# HVAC8new.net
KiCad netlist of a schematic drawn in EAGLE
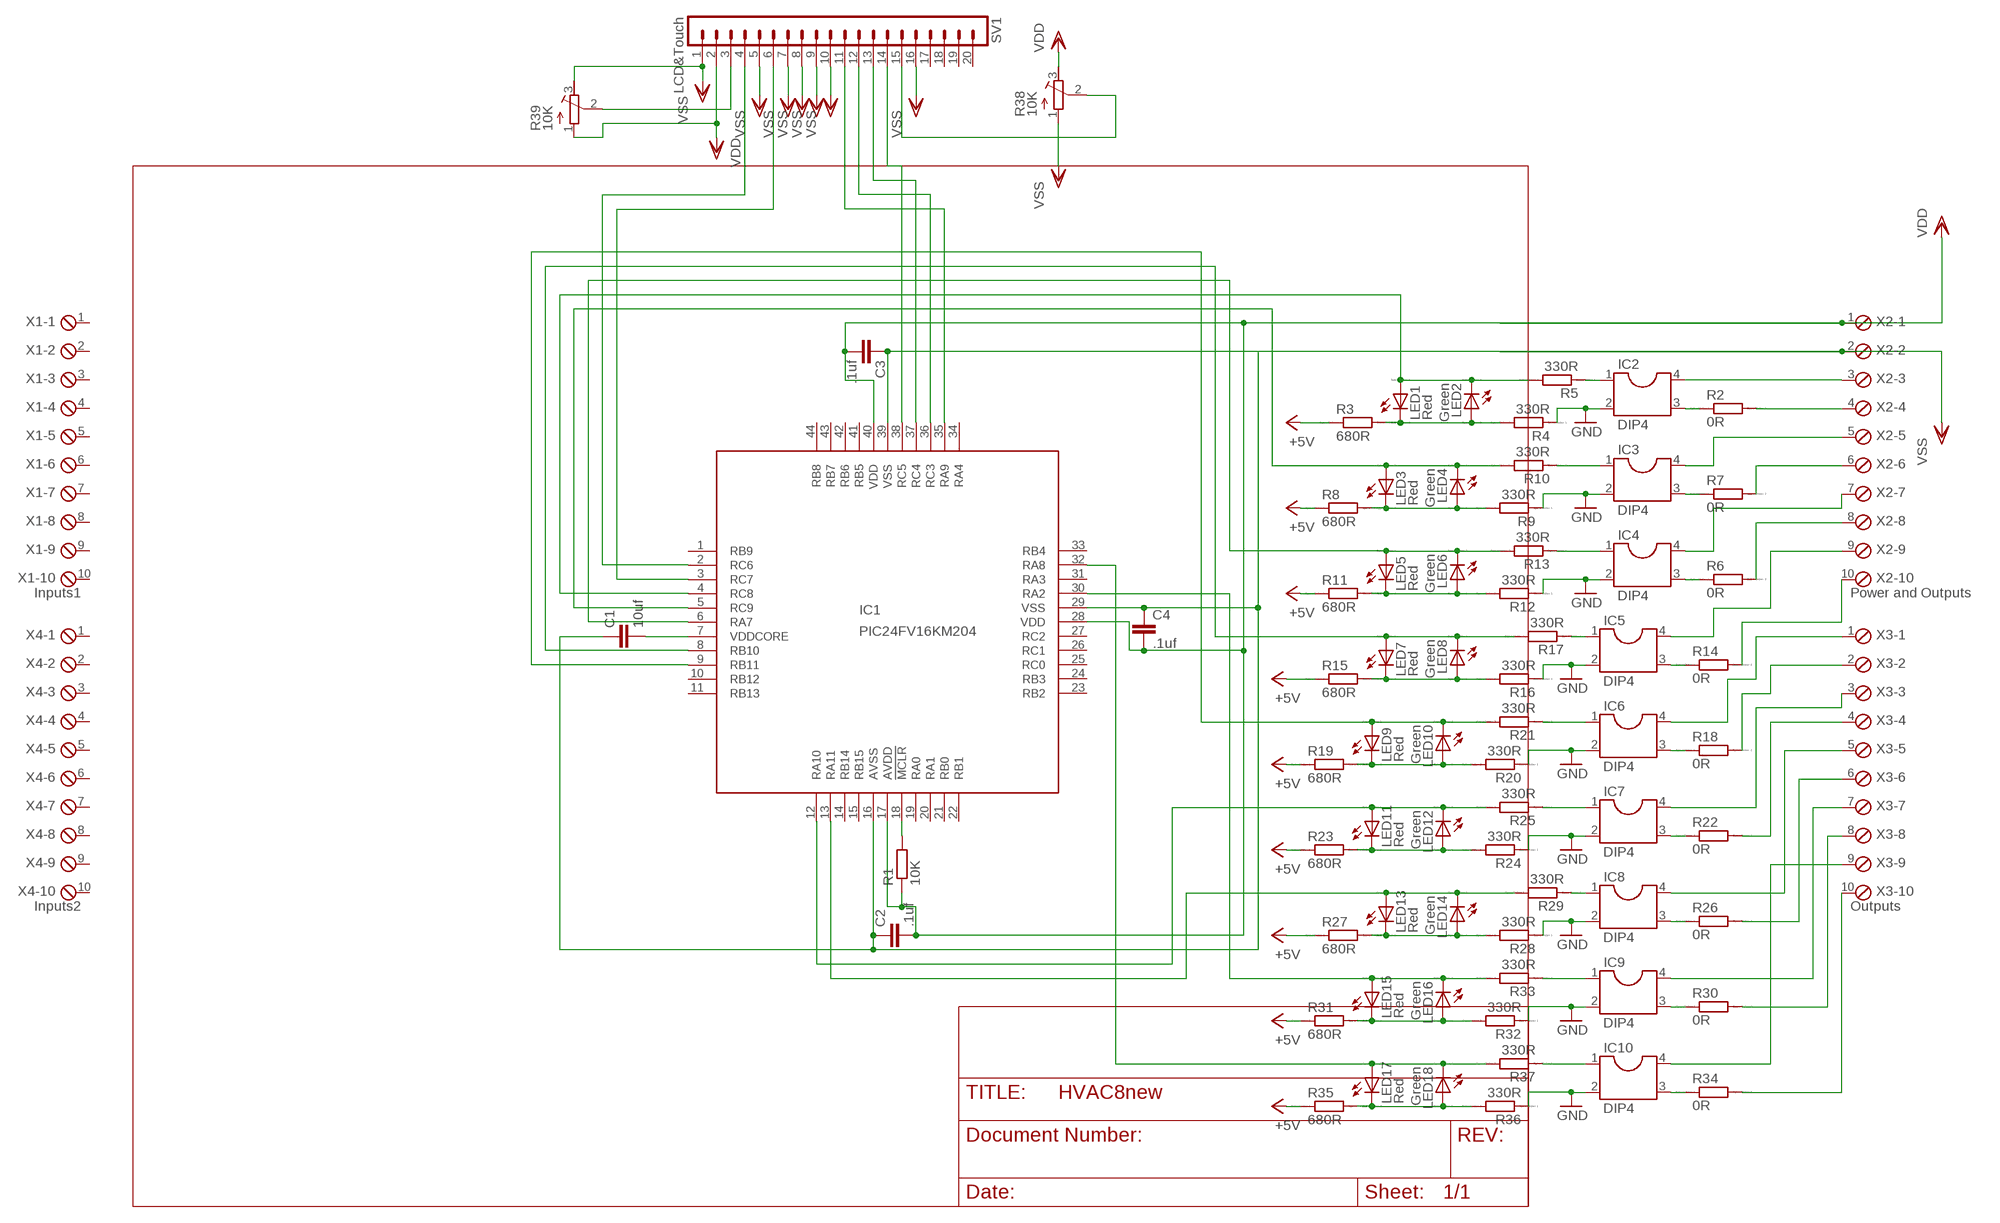
[diagram p0: schematic, sheet 1]

(export (version "E")
  (design (tool "Eeschema 10.0.6"))
  (components
    (comp (ref "C1")
      (value "10uf")
      (footprint "eagle-import:C1206")
      (libsource (lib "eagle-import") (part "C-EUC1206"))
    )
    (comp (ref "C2")
      (value ".1uf")
      (footprint "eagle-import:C1206")
      (libsource (lib "eagle-import") (part "C-EUC1206"))
    )
    (comp (ref "C3")
      (value ".1uf")
      (footprint "eagle-import:C1206")
      (libsource (lib "eagle-import") (part "C-EUC1206"))
    )
    (comp (ref "C4")
      (value ".1uf")
      (footprint "eagle-import:C1206")
      (libsource (lib "eagle-import") (part "C-EUC1206"))
    )
    (comp (ref "IC1")
      (value "PIC24FV16KM204")
      (footprint "eagle-import:TQFP44")
      (libsource (lib "eagle-import") (part "PIC24FV16KM204"))
    )
    (comp (ref "IC2")
      (value "DIP4")
      (footprint "eagle-import:SOCKET-04")
      (libsource (lib "eagle-import") (part "DIL4S"))
    )
    (comp (ref "IC3")
      (value "DIP4")
      (footprint "eagle-import:SOCKET-04")
      (libsource (lib "eagle-import") (part "DIL4S"))
    )
    (comp (ref "IC4")
      (value "DIP4")
      (footprint "eagle-import:SOCKET-04")
      (libsource (lib "eagle-import") (part "DIL4S"))
    )
    (comp (ref "IC5")
      (value "DIP4")
      (footprint "eagle-import:SOCKET-04")
      (libsource (lib "eagle-import") (part "DIL4S"))
    )
    (comp (ref "IC6")
      (value "DIP4")
      (footprint "eagle-import:SOCKET-04")
      (libsource (lib "eagle-import") (part "DIL4S"))
    )
    (comp (ref "IC7")
      (value "DIP4")
      (footprint "eagle-import:SOCKET-04")
      (libsource (lib "eagle-import") (part "DIL4S"))
    )
    (comp (ref "IC8")
      (value "DIP4")
      (footprint "eagle-import:SOCKET-04")
      (libsource (lib "eagle-import") (part "DIL4S"))
    )
    (comp (ref "IC9")
      (value "DIP4")
      (footprint "eagle-import:SOCKET-04")
      (libsource (lib "eagle-import") (part "DIL4S"))
    )
    (comp (ref "IC10")
      (value "DIP4")
      (footprint "eagle-import:SOCKET-04")
      (libsource (lib "eagle-import") (part "DIL4S"))
    )
    (comp (ref "LED1")
      (value "Red")
      (footprint "eagle-import:LED_1206")
      (libsource (lib "eagle-import") (part "LED_E"))
    )
    (comp (ref "LED2")
      (value "Green")
      (footprint "eagle-import:LED_1206")
      (libsource (lib "eagle-import") (part "LED_E"))
    )
    (comp (ref "LED3")
      (value "Red")
      (footprint "eagle-import:LED_1206")
      (libsource (lib "eagle-import") (part "LED_E"))
    )
    (comp (ref "LED4")
      (value "Green")
      (footprint "eagle-import:LED_1206")
      (libsource (lib "eagle-import") (part "LED_E"))
    )
    (comp (ref "LED5")
      (value "Red")
      (footprint "eagle-import:LED_1206")
      (libsource (lib "eagle-import") (part "LED_E"))
    )
    (comp (ref "LED6")
      (value "Green")
      (footprint "eagle-import:LED_1206")
      (libsource (lib "eagle-import") (part "LED_E"))
    )
    (comp (ref "LED7")
      (value "Red")
      (footprint "eagle-import:LED_1206")
      (libsource (lib "eagle-import") (part "LED_E"))
    )
    (comp (ref "LED8")
      (value "Green")
      (footprint "eagle-import:LED_1206")
      (libsource (lib "eagle-import") (part "LED_E"))
    )
    (comp (ref "LED9")
      (value "Red")
      (footprint "eagle-import:LED_1206")
      (libsource (lib "eagle-import") (part "LED_E"))
    )
    (comp (ref "LED10")
      (value "Green")
      (footprint "eagle-import:LED_1206")
      (libsource (lib "eagle-import") (part "LED_E"))
    )
    (comp (ref "LED11")
      (value "Red")
      (footprint "eagle-import:LED_1206")
      (libsource (lib "eagle-import") (part "LED_E"))
    )
    (comp (ref "LED12")
      (value "Green")
      (footprint "eagle-import:LED_1206")
      (libsource (lib "eagle-import") (part "LED_E"))
    )
    (comp (ref "LED13")
      (value "Red")
      (footprint "eagle-import:LED_1206")
      (libsource (lib "eagle-import") (part "LED_E"))
    )
    (comp (ref "LED14")
      (value "Green")
      (footprint "eagle-import:LED_1206")
      (libsource (lib "eagle-import") (part "LED_E"))
    )
    (comp (ref "LED15")
      (value "Red")
      (footprint "eagle-import:LED_1206")
      (libsource (lib "eagle-import") (part "LED_E"))
    )
    (comp (ref "LED16")
      (value "Green")
      (footprint "eagle-import:LED_1206")
      (libsource (lib "eagle-import") (part "LED_E"))
    )
    (comp (ref "LED17")
      (value "Red")
      (footprint "eagle-import:LED_1206")
      (libsource (lib "eagle-import") (part "LED_E"))
    )
    (comp (ref "LED18")
      (value "Green")
      (footprint "eagle-import:LED_1206")
      (libsource (lib "eagle-import") (part "LED_E"))
    )
    (comp (ref "R1")
      (value "10K")
      (footprint "eagle-import:R1206")
      (libsource (lib "eagle-import") (part "R-EU_R1206"))
    )
    (comp (ref "R2")
      (value "0R")
      (footprint "eagle-import:R1206")
      (libsource (lib "eagle-import") (part "RR1206"))
    )
    (comp (ref "R3")
      (value "680R")
      (footprint "eagle-import:R1206")
      (libsource (lib "eagle-import") (part "RR1206"))
    )
    (comp (ref "R4")
      (value "330R")
      (footprint "eagle-import:R1206")
      (libsource (lib "eagle-import") (part "RR1206"))
    )
    (comp (ref "R5")
      (value "330R")
      (footprint "eagle-import:R1206")
      (libsource (lib "eagle-import") (part "RR1206"))
    )
    (comp (ref "R6")
      (value "0R")
      (footprint "eagle-import:R1206")
      (libsource (lib "eagle-import") (part "RR1206"))
    )
    (comp (ref "R7")
      (value "0R")
      (footprint "eagle-import:R1206")
      (libsource (lib "eagle-import") (part "RR1206"))
    )
    (comp (ref "R8")
      (value "680R")
      (footprint "eagle-import:R1206")
      (libsource (lib "eagle-import") (part "RR1206"))
    )
    (comp (ref "R9")
      (value "330R")
      (footprint "eagle-import:R1206")
      (libsource (lib "eagle-import") (part "RR1206"))
    )
    (comp (ref "R10")
      (value "330R")
      (footprint "eagle-import:R1206")
      (libsource (lib "eagle-import") (part "RR1206"))
    )
    (comp (ref "R11")
      (value "680R")
      (footprint "eagle-import:R1206")
      (libsource (lib "eagle-import") (part "RR1206"))
    )
    (comp (ref "R12")
      (value "330R")
      (footprint "eagle-import:R1206")
      (libsource (lib "eagle-import") (part "RR1206"))
    )
    (comp (ref "R13")
      (value "330R")
      (footprint "eagle-import:R1206")
      (libsource (lib "eagle-import") (part "RR1206"))
    )
    (comp (ref "R14")
      (value "0R")
      (footprint "eagle-import:R1206")
      (libsource (lib "eagle-import") (part "RR1206"))
    )
    (comp (ref "R15")
      (value "680R")
      (footprint "eagle-import:R1206")
      (libsource (lib "eagle-import") (part "RR1206"))
    )
    (comp (ref "R16")
      (value "330R")
      (footprint "eagle-import:R1206")
      (libsource (lib "eagle-import") (part "RR1206"))
    )
    (comp (ref "R17")
      (value "330R")
      (footprint "eagle-import:R1206")
      (libsource (lib "eagle-import") (part "RR1206"))
    )
    (comp (ref "R18")
      (value "0R")
      (footprint "eagle-import:R1206")
      (libsource (lib "eagle-import") (part "RR1206"))
    )
    (comp (ref "R19")
      (value "680R")
      (footprint "eagle-import:R1206")
      (libsource (lib "eagle-import") (part "RR1206"))
    )
    (comp (ref "R20")
      (value "330R")
      (footprint "eagle-import:R1206")
      (libsource (lib "eagle-import") (part "RR1206"))
    )
    (comp (ref "R21")
      (value "330R")
      (footprint "eagle-import:R1206")
      (libsource (lib "eagle-import") (part "RR1206"))
    )
    (comp (ref "R22")
      (value "0R")
      (footprint "eagle-import:R1206")
      (libsource (lib "eagle-import") (part "RR1206"))
    )
    (comp (ref "R23")
      (value "680R")
      (footprint "eagle-import:R1206")
      (libsource (lib "eagle-import") (part "RR1206"))
    )
    (comp (ref "R24")
      (value "330R")
      (footprint "eagle-import:R1206")
      (libsource (lib "eagle-import") (part "RR1206"))
    )
    (comp (ref "R25")
      (value "330R")
      (footprint "eagle-import:R1206")
      (libsource (lib "eagle-import") (part "RR1206"))
    )
    (comp (ref "R26")
      (value "0R")
      (footprint "eagle-import:R1206")
      (libsource (lib "eagle-import") (part "RR1206"))
    )
    (comp (ref "R27")
      (value "680R")
      (footprint "eagle-import:R1206")
      (libsource (lib "eagle-import") (part "RR1206"))
    )
    (comp (ref "R28")
      (value "330R")
      (footprint "eagle-import:R1206")
      (libsource (lib "eagle-import") (part "RR1206"))
    )
    (comp (ref "R29")
      (value "330R")
      (footprint "eagle-import:R1206")
      (libsource (lib "eagle-import") (part "RR1206"))
    )
    (comp (ref "R30")
      (value "0R")
      (footprint "eagle-import:R1206")
      (libsource (lib "eagle-import") (part "RR1206"))
    )
    (comp (ref "R31")
      (value "680R")
      (footprint "eagle-import:R1206")
      (libsource (lib "eagle-import") (part "RR1206"))
    )
    (comp (ref "R32")
      (value "330R")
      (footprint "eagle-import:R1206")
      (libsource (lib "eagle-import") (part "RR1206"))
    )
    (comp (ref "R33")
      (value "330R")
      (footprint "eagle-import:R1206")
      (libsource (lib "eagle-import") (part "RR1206"))
    )
    (comp (ref "R34")
      (value "0R")
      (footprint "eagle-import:R1206")
      (libsource (lib "eagle-import") (part "RR1206"))
    )
    (comp (ref "R35")
      (value "680R")
      (footprint "eagle-import:R1206")
      (libsource (lib "eagle-import") (part "RR1206"))
    )
    (comp (ref "R36")
      (value "330R")
      (footprint "eagle-import:R1206")
      (libsource (lib "eagle-import") (part "RR1206"))
    )
    (comp (ref "R37")
      (value "330R")
      (footprint "eagle-import:R1206")
      (libsource (lib "eagle-import") (part "RR1206"))
    )
    (comp (ref "R38")
      (value "10K")
      (footprint "eagle-import:RTRIM3296W")
      (libsource (lib "eagle-import") (part "R-TRIMM3296W"))
    )
    (comp (ref "R39")
      (value "10K")
      (footprint "eagle-import:RTRIM3296W")
      (libsource (lib "eagle-import") (part "R-TRIMM3296W"))
    )
    (comp (ref "SV1")
      (value "LCD&Touch")
      (footprint "eagle-import:MA20-1")
      (libsource (lib "eagle-import") (part "MA20-1"))
    )
    (comp (ref "X1")
      (value "Inputs1")
      (footprint "eagle-import:10POL254")
      (libsource (lib "eagle-import") (part "MPT10"))
    )
    (comp (ref "X2")
      (value "Power and Outputs")
      (footprint "eagle-import:10POL254")
      (libsource (lib "eagle-import") (part "MPT10"))
    )
    (comp (ref "X3")
      (value "Outputs")
      (footprint "eagle-import:10POL254")
      (libsource (lib "eagle-import") (part "MPT10"))
    )
    (comp (ref "X4")
      (value "Inputs2")
      (footprint "eagle-import:10POL254")
      (libsource (lib "eagle-import") (part "MPT10"))
    )
  )
  (nets
    (net (code "1") (name "+5V") (class "Default")
      (node (ref "R11") (pin "1") (pinfunction "1_1") (pintype "passive"))
      (node (ref "R15") (pin "1") (pinfunction "1_1") (pintype "passive"))
      (node (ref "R19") (pin "1") (pinfunction "1_1") (pintype "passive"))
      (node (ref "R23") (pin "1") (pinfunction "1_1") (pintype "passive"))
      (node (ref "R27") (pin "1") (pinfunction "1_1") (pintype "passive"))
      (node (ref "R3") (pin "1") (pinfunction "1_1") (pintype "passive"))
      (node (ref "R31") (pin "1") (pinfunction "1_1") (pintype "passive"))
      (node (ref "R35") (pin "1") (pinfunction "1_1") (pintype "passive"))
      (node (ref "R8") (pin "1") (pinfunction "1_1") (pintype "passive"))
    )
    (net (code "2") (name "GND") (class "Default")
      (node (ref "IC10") (pin "2") (pinfunction "2_2") (pintype "passive"))
      (node (ref "IC2") (pin "2") (pinfunction "2_2") (pintype "passive"))
      (node (ref "IC3") (pin "2") (pinfunction "2_2") (pintype "passive"))
      (node (ref "IC4") (pin "2") (pinfunction "2_2") (pintype "passive"))
      (node (ref "IC5") (pin "2") (pinfunction "2_2") (pintype "passive"))
      (node (ref "IC6") (pin "2") (pinfunction "2_2") (pintype "passive"))
      (node (ref "IC7") (pin "2") (pinfunction "2_2") (pintype "passive"))
      (node (ref "IC8") (pin "2") (pinfunction "2_2") (pintype "passive"))
      (node (ref "IC9") (pin "2") (pinfunction "2_2") (pintype "passive"))
      (node (ref "R12") (pin "1") (pinfunction "1_1") (pintype "passive"))
      (node (ref "R16") (pin "1") (pinfunction "1_1") (pintype "passive"))
      (node (ref "R20") (pin "1") (pinfunction "1_1") (pintype "passive"))
      (node (ref "R24") (pin "1") (pinfunction "1_1") (pintype "passive"))
      (node (ref "R28") (pin "1") (pinfunction "1_1") (pintype "passive"))
      (node (ref "R32") (pin "1") (pinfunction "1_1") (pintype "passive"))
      (node (ref "R36") (pin "1") (pinfunction "1_1") (pintype "passive"))
      (node (ref "R4") (pin "1") (pinfunction "1_1") (pintype "passive"))
      (node (ref "R9") (pin "1") (pinfunction "1_1") (pintype "passive"))
    )
    (net (code "3") (name "Net-(IC1-RA2)") (class "Default")
      (node (ref "IC1") (pin "30") (pinfunction "RA2_30") (pintype "bidirectional"))
      (node (ref "LED15") (pin "A") (pinfunction "A_A") (pintype "passive"))
      (node (ref "LED16") (pin "C") (pinfunction "C_C") (pintype "passive"))
      (node (ref "R33") (pin "2") (pinfunction "2_2") (pintype "passive"))
    )
    (net (code "4") (name "Net-(IC1-RA7)") (class "Default")
      (node (ref "IC1") (pin "6") (pinfunction "RA7_6") (pintype "bidirectional"))
      (node (ref "LED5") (pin "A") (pinfunction "A_A") (pintype "passive"))
      (node (ref "LED6") (pin "C") (pinfunction "C_C") (pintype "passive"))
      (node (ref "R13") (pin "2") (pinfunction "2_2") (pintype "passive"))
    )
    (net (code "5") (name "Net-(IC1-RA8)") (class "Default")
      (node (ref "IC1") (pin "32") (pinfunction "RA8_32") (pintype "bidirectional"))
      (node (ref "LED17") (pin "A") (pinfunction "A_A") (pintype "passive"))
      (node (ref "LED18") (pin "C") (pinfunction "C_C") (pintype "passive"))
      (node (ref "R37") (pin "2") (pinfunction "2_2") (pintype "passive"))
    )
    (net (code "6") (name "Net-(IC1-RA9)") (class "Default")
      (node (ref "IC1") (pin "35") (pinfunction "RA9_35") (pintype "bidirectional"))
      (node (ref "SV1") (pin "11") (pinfunction "11_11") (pintype "passive"))
    )
    (net (code "7") (name "Net-(IC1-RA10)") (class "Default")
      (node (ref "IC1") (pin "12") (pinfunction "RA10_12") (pintype "bidirectional"))
      (node (ref "LED11") (pin "A") (pinfunction "A_A") (pintype "passive"))
      (node (ref "LED12") (pin "C") (pinfunction "C_C") (pintype "passive"))
      (node (ref "R25") (pin "2") (pinfunction "2_2") (pintype "passive"))
    )
    (net (code "8") (name "Net-(IC1-RA11)") (class "Default")
      (node (ref "IC1") (pin "13") (pinfunction "RA11_13") (pintype "bidirectional"))
      (node (ref "LED13") (pin "A") (pinfunction "A_A") (pintype "passive"))
      (node (ref "LED14") (pin "C") (pinfunction "C_C") (pintype "passive"))
      (node (ref "R29") (pin "2") (pinfunction "2_2") (pintype "passive"))
    )
    (net (code "9") (name "Net-(IC1-RB10)") (class "Default")
      (node (ref "IC1") (pin "8") (pinfunction "RB10_8") (pintype "bidirectional"))
      (node (ref "LED7") (pin "A") (pinfunction "A_A") (pintype "passive"))
      (node (ref "LED8") (pin "C") (pinfunction "C_C") (pintype "passive"))
      (node (ref "R17") (pin "2") (pinfunction "2_2") (pintype "passive"))
    )
    (net (code "10") (name "Net-(IC1-RB11)") (class "Default")
      (node (ref "IC1") (pin "9") (pinfunction "RB11_9") (pintype "bidirectional"))
      (node (ref "LED10") (pin "C") (pinfunction "C_C") (pintype "passive"))
      (node (ref "LED9") (pin "A") (pinfunction "A_A") (pintype "passive"))
      (node (ref "R21") (pin "2") (pinfunction "2_2") (pintype "passive"))
    )
    (net (code "11") (name "Net-(IC1-RC3)") (class "Default")
      (node (ref "IC1") (pin "36") (pinfunction "RC3_36") (pintype "bidirectional"))
      (node (ref "SV1") (pin "12") (pinfunction "12_12") (pintype "passive"))
    )
    (net (code "12") (name "Net-(IC1-RC4)") (class "Default")
      (node (ref "IC1") (pin "37") (pinfunction "RC4_37") (pintype "bidirectional"))
      (node (ref "SV1") (pin "13") (pinfunction "13_13") (pintype "passive"))
    )
    (net (code "13") (name "Net-(IC1-RC5)") (class "Default")
      (node (ref "IC1") (pin "38") (pinfunction "RC5_38") (pintype "bidirectional"))
      (node (ref "SV1") (pin "14") (pinfunction "14_14") (pintype "passive"))
    )
    (net (code "14") (name "Net-(IC1-RC6)") (class "Default")
      (node (ref "IC1") (pin "2") (pinfunction "RC6_2") (pintype "bidirectional"))
      (node (ref "SV1") (pin "4") (pinfunction "4_4") (pintype "passive"))
    )
    (net (code "15") (name "Net-(IC1-RC7)") (class "Default")
      (node (ref "IC1") (pin "3") (pinfunction "RC7_3") (pintype "bidirectional"))
      (node (ref "SV1") (pin "6") (pinfunction "6_6") (pintype "passive"))
    )
    (net (code "16") (name "Net-(IC1-RC8)") (class "Default")
      (node (ref "IC1") (pin "4") (pinfunction "RC8_4") (pintype "bidirectional"))
      (node (ref "LED1") (pin "A") (pinfunction "A_A") (pintype "passive"))
      (node (ref "LED2") (pin "C") (pinfunction "C_C") (pintype "passive"))
      (node (ref "R5") (pin "2") (pinfunction "2_2") (pintype "passive"))
    )
    (net (code "17") (name "Net-(IC1-RC9)") (class "Default")
      (node (ref "IC1") (pin "5") (pinfunction "RC9_5") (pintype "bidirectional"))
      (node (ref "LED3") (pin "A") (pinfunction "A_A") (pintype "passive"))
      (node (ref "LED4") (pin "C") (pinfunction "C_C") (pintype "passive"))
      (node (ref "R10") (pin "2") (pinfunction "2_2") (pintype "passive"))
    )
    (net (code "18") (name "Net-(IC1-VDDCORE)") (class "Default")
      (node (ref "C1") (pin "2") (pinfunction "2_2") (pintype "passive"))
      (node (ref "IC1") (pin "7") (pinfunction "VDDCORE_7") (pintype "power_in"))
    )
    (net (code "19") (name "Net-(IC1-~{MCLR})") (class "Default")
      (node (ref "IC1") (pin "18") (pinfunction "~{MCLR}_18") (pintype "bidirectional"))
      (node (ref "R1") (pin "2") (pinfunction "2_2") (pintype "passive"))
    )
    (net (code "20") (name "Net-(IC2-Pad1)") (class "Default")
      (node (ref "IC2") (pin "1") (pinfunction "1_1") (pintype "passive"))
      (node (ref "R5") (pin "1") (pinfunction "1_1") (pintype "passive"))
    )
    (net (code "21") (name "Net-(IC2-Pad3)") (class "Default")
      (node (ref "IC2") (pin "3") (pinfunction "3_3") (pintype "passive"))
      (node (ref "R2") (pin "1") (pinfunction "1_1") (pintype "passive"))
    )
    (net (code "22") (name "Net-(IC3-Pad1)") (class "Default")
      (node (ref "IC3") (pin "1") (pinfunction "1_1") (pintype "passive"))
      (node (ref "R10") (pin "1") (pinfunction "1_1") (pintype "passive"))
    )
    (net (code "23") (name "Net-(IC3-Pad3)") (class "Default")
      (node (ref "IC3") (pin "3") (pinfunction "3_3") (pintype "passive"))
      (node (ref "R7") (pin "1") (pinfunction "1_1") (pintype "passive"))
    )
    (net (code "24") (name "Net-(IC4-Pad1)") (class "Default")
      (node (ref "IC4") (pin "1") (pinfunction "1_1") (pintype "passive"))
      (node (ref "R13") (pin "1") (pinfunction "1_1") (pintype "passive"))
    )
    (net (code "25") (name "Net-(IC4-Pad3)") (class "Default")
      (node (ref "IC4") (pin "3") (pinfunction "3_3") (pintype "passive"))
      (node (ref "R6") (pin "1") (pinfunction "1_1") (pintype "passive"))
    )
    (net (code "26") (name "Net-(IC5-Pad1)") (class "Default")
      (node (ref "IC5") (pin "1") (pinfunction "1_1") (pintype "passive"))
      (node (ref "R17") (pin "1") (pinfunction "1_1") (pintype "passive"))
    )
    (net (code "27") (name "Net-(IC5-Pad3)") (class "Default")
      (node (ref "IC5") (pin "3") (pinfunction "3_3") (pintype "passive"))
      (node (ref "R14") (pin "1") (pinfunction "1_1") (pintype "passive"))
    )
    (net (code "28") (name "Net-(IC6-Pad1)") (class "Default")
      (node (ref "IC6") (pin "1") (pinfunction "1_1") (pintype "passive"))
      (node (ref "R21") (pin "1") (pinfunction "1_1") (pintype "passive"))
    )
    (net (code "29") (name "Net-(IC6-Pad3)") (class "Default")
      (node (ref "IC6") (pin "3") (pinfunction "3_3") (pintype "passive"))
      (node (ref "R18") (pin "1") (pinfunction "1_1") (pintype "passive"))
    )
    (net (code "30") (name "Net-(IC6-Pad4)") (class "Default")
      (node (ref "IC6") (pin "4") (pinfunction "4_4") (pintype "passive"))
      (node (ref "X3") (pin "1") (pinfunction "1_1") (pintype "passive"))
    )
    (net (code "31") (name "Net-(IC7-Pad1)") (class "Default")
      (node (ref "IC7") (pin "1") (pinfunction "1_1") (pintype "passive"))
      (node (ref "R25") (pin "1") (pinfunction "1_1") (pintype "passive"))
    )
    (net (code "32") (name "Net-(IC7-Pad3)") (class "Default")
      (node (ref "IC7") (pin "3") (pinfunction "3_3") (pintype "passive"))
      (node (ref "R22") (pin "1") (pinfunction "1_1") (pintype "passive"))
    )
    (net (code "33") (name "Net-(IC8-Pad1)") (class "Default")
      (node (ref "IC8") (pin "1") (pinfunction "1_1") (pintype "passive"))
      (node (ref "R29") (pin "1") (pinfunction "1_1") (pintype "passive"))
    )
    (net (code "34") (name "Net-(IC8-Pad3)") (class "Default")
      (node (ref "IC8") (pin "3") (pinfunction "3_3") (pintype "passive"))
      (node (ref "R26") (pin "1") (pinfunction "1_1") (pintype "passive"))
    )
    (net (code "35") (name "Net-(IC9-Pad1)") (class "Default")
      (node (ref "IC9") (pin "1") (pinfunction "1_1") (pintype "passive"))
      (node (ref "R33") (pin "1") (pinfunction "1_1") (pintype "passive"))
    )
    (net (code "36") (name "Net-(IC9-Pad3)") (class "Default")
      (node (ref "IC9") (pin "3") (pinfunction "3_3") (pintype "passive"))
      (node (ref "R30") (pin "1") (pinfunction "1_1") (pintype "passive"))
    )
    (net (code "37") (name "Net-(IC10-Pad1)") (class "Default")
      (node (ref "IC10") (pin "1") (pinfunction "1_1") (pintype "passive"))
      (node (ref "R37") (pin "1") (pinfunction "1_1") (pintype "passive"))
    )
    (net (code "38") (name "Net-(IC10-Pad3)") (class "Default")
      (node (ref "IC10") (pin "3") (pinfunction "3_3") (pintype "passive"))
      (node (ref "R34") (pin "1") (pinfunction "1_1") (pintype "passive"))
    )
    (net (code "39") (name "Net-(LED1-PadC)") (class "Default")
      (node (ref "LED1") (pin "C") (pinfunction "C_C") (pintype "passive"))
      (node (ref "LED2") (pin "A") (pinfunction "A_A") (pintype "passive"))
      (node (ref "R3") (pin "2") (pinfunction "2_2") (pintype "passive"))
      (node (ref "R4") (pin "2") (pinfunction "2_2") (pintype "passive"))
    )
    (net (code "40") (name "Net-(LED3-PadC)") (class "Default")
      (node (ref "LED3") (pin "C") (pinfunction "C_C") (pintype "passive"))
      (node (ref "LED4") (pin "A") (pinfunction "A_A") (pintype "passive"))
      (node (ref "R8") (pin "2") (pinfunction "2_2") (pintype "passive"))
      (node (ref "R9") (pin "2") (pinfunction "2_2") (pintype "passive"))
    )
    (net (code "41") (name "Net-(LED5-PadC)") (class "Default")
      (node (ref "LED5") (pin "C") (pinfunction "C_C") (pintype "passive"))
      (node (ref "LED6") (pin "A") (pinfunction "A_A") (pintype "passive"))
      (node (ref "R11") (pin "2") (pinfunction "2_2") (pintype "passive"))
      (node (ref "R12") (pin "2") (pinfunction "2_2") (pintype "passive"))
    )
    (net (code "42") (name "Net-(LED7-PadC)") (class "Default")
      (node (ref "LED7") (pin "C") (pinfunction "C_C") (pintype "passive"))
      (node (ref "LED8") (pin "A") (pinfunction "A_A") (pintype "passive"))
      (node (ref "R15") (pin "2") (pinfunction "2_2") (pintype "passive"))
      (node (ref "R16") (pin "2") (pinfunction "2_2") (pintype "passive"))
    )
    (net (code "43") (name "Net-(LED10-PadA)") (class "Default")
      (node (ref "LED10") (pin "A") (pinfunction "A_A") (pintype "passive"))
      (node (ref "LED9") (pin "C") (pinfunction "C_C") (pintype "passive"))
      (node (ref "R19") (pin "2") (pinfunction "2_2") (pintype "passive"))
      (node (ref "R20") (pin "2") (pinfunction "2_2") (pintype "passive"))
    )
    (net (code "44") (name "Net-(LED11-PadC)") (class "Default")
      (node (ref "LED11") (pin "C") (pinfunction "C_C") (pintype "passive"))
      (node (ref "LED12") (pin "A") (pinfunction "A_A") (pintype "passive"))
      (node (ref "R23") (pin "2") (pinfunction "2_2") (pintype "passive"))
      (node (ref "R24") (pin "2") (pinfunction "2_2") (pintype "passive"))
    )
    (net (code "45") (name "Net-(LED13-PadC)") (class "Default")
      (node (ref "LED13") (pin "C") (pinfunction "C_C") (pintype "passive"))
      (node (ref "LED14") (pin "A") (pinfunction "A_A") (pintype "passive"))
      (node (ref "R27") (pin "2") (pinfunction "2_2") (pintype "passive"))
      (node (ref "R28") (pin "2") (pinfunction "2_2") (pintype "passive"))
    )
    (net (code "46") (name "Net-(LED15-PadC)") (class "Default")
      (node (ref "LED15") (pin "C") (pinfunction "C_C") (pintype "passive"))
      (node (ref "LED16") (pin "A") (pinfunction "A_A") (pintype "passive"))
      (node (ref "R31") (pin "2") (pinfunction "2_2") (pintype "passive"))
      (node (ref "R32") (pin "2") (pinfunction "2_2") (pintype "passive"))
    )
    (net (code "47") (name "Net-(LED17-PadC)") (class "Default")
      (node (ref "LED17") (pin "C") (pinfunction "C_C") (pintype "passive"))
      (node (ref "LED18") (pin "A") (pinfunction "A_A") (pintype "passive"))
      (node (ref "R35") (pin "2") (pinfunction "2_2") (pintype "passive"))
      (node (ref "R36") (pin "2") (pinfunction "2_2") (pintype "passive"))
    )
    (net (code "48") (name "Net-(R38-S)") (class "Default")
      (node (ref "R38") (pin "2") (pinfunction "S_2") (pintype "passive"))
      (node (ref "SV1") (pin "15") (pinfunction "15_15") (pintype "passive"))
    )
    (net (code "49") (name "Net-(R39-S)") (class "Default")
      (node (ref "R39") (pin "2") (pinfunction "S_2") (pintype "passive"))
      (node (ref "SV1") (pin "3") (pinfunction "3_3") (pintype "passive"))
    )
    (net (code "50") (name "Net-(X2B-1)") (class "Default")
      (node (ref "R14") (pin "2") (pinfunction "2_2") (pintype "passive"))
      (node (ref "X2") (pin "10") (pinfunction "1_10") (pintype "passive"))
    )
    (net (code "51") (name "Net-(X2D-1)") (class "Default")
      (node (ref "IC2") (pin "4") (pinfunction "4_4") (pintype "passive"))
      (node (ref "X2") (pin "3") (pinfunction "1_3") (pintype "passive"))
    )
    (net (code "52") (name "Net-(X2E-1)") (class "Default")
      (node (ref "R2") (pin "2") (pinfunction "2_2") (pintype "passive"))
      (node (ref "X2") (pin "4") (pinfunction "1_4") (pintype "passive"))
    )
    (net (code "53") (name "Net-(X2F-1)") (class "Default")
      (node (ref "IC3") (pin "4") (pinfunction "4_4") (pintype "passive"))
      (node (ref "X2") (pin "5") (pinfunction "1_5") (pintype "passive"))
    )
    (net (code "54") (name "Net-(X2G-1)") (class "Default")
      (node (ref "R7") (pin "2") (pinfunction "2_2") (pintype "passive"))
      (node (ref "X2") (pin "6") (pinfunction "1_6") (pintype "passive"))
    )
    (net (code "55") (name "Net-(X2H-1)") (class "Default")
      (node (ref "IC4") (pin "4") (pinfunction "4_4") (pintype "passive"))
      (node (ref "X2") (pin "7") (pinfunction "1_7") (pintype "passive"))
    )
    (net (code "56") (name "Net-(X2I-1)") (class "Default")
      (node (ref "R6") (pin "2") (pinfunction "2_2") (pintype "passive"))
      (node (ref "X2") (pin "8") (pinfunction "1_8") (pintype "passive"))
    )
    (net (code "57") (name "Net-(X2J-1)") (class "Default")
      (node (ref "IC5") (pin "4") (pinfunction "4_4") (pintype "passive"))
      (node (ref "X2") (pin "9") (pinfunction "1_9") (pintype "passive"))
    )
    (net (code "58") (name "Net-(X3B-1)") (class "Default")
      (node (ref "R34") (pin "2") (pinfunction "2_2") (pintype "passive"))
      (node (ref "X3") (pin "10") (pinfunction "1_10") (pintype "passive"))
    )
    (net (code "59") (name "Net-(X3C-1)") (class "Default")
      (node (ref "R18") (pin "2") (pinfunction "2_2") (pintype "passive"))
      (node (ref "X3") (pin "2") (pinfunction "1_2") (pintype "passive"))
    )
    (net (code "60") (name "Net-(X3D-1)") (class "Default")
      (node (ref "IC7") (pin "4") (pinfunction "4_4") (pintype "passive"))
      (node (ref "X3") (pin "3") (pinfunction "1_3") (pintype "passive"))
    )
    (net (code "61") (name "Net-(X3E-1)") (class "Default")
      (node (ref "R22") (pin "2") (pinfunction "2_2") (pintype "passive"))
      (node (ref "X3") (pin "4") (pinfunction "1_4") (pintype "passive"))
    )
    (net (code "62") (name "Net-(X3F-1)") (class "Default")
      (node (ref "IC8") (pin "4") (pinfunction "4_4") (pintype "passive"))
      (node (ref "X3") (pin "5") (pinfunction "1_5") (pintype "passive"))
    )
    (net (code "63") (name "Net-(X3G-1)") (class "Default")
      (node (ref "R26") (pin "2") (pinfunction "2_2") (pintype "passive"))
      (node (ref "X3") (pin "6") (pinfunction "1_6") (pintype "passive"))
    )
    (net (code "64") (name "Net-(X3H-1)") (class "Default")
      (node (ref "IC9") (pin "4") (pinfunction "4_4") (pintype "passive"))
      (node (ref "X3") (pin "7") (pinfunction "1_7") (pintype "passive"))
    )
    (net (code "65") (name "Net-(X3I-1)") (class "Default")
      (node (ref "R30") (pin "2") (pinfunction "2_2") (pintype "passive"))
      (node (ref "X3") (pin "8") (pinfunction "1_8") (pintype "passive"))
    )
    (net (code "66") (name "Net-(X3J-1)") (class "Default")
      (node (ref "IC10") (pin "4") (pinfunction "4_4") (pintype "passive"))
      (node (ref "X3") (pin "9") (pinfunction "1_9") (pintype "passive"))
    )
    (net (code "67") (name "VDD") (class "Default")
      (node (ref "C2") (pin "2") (pinfunction "2_2") (pintype "passive"))
      (node (ref "C3") (pin "2") (pinfunction "2_2") (pintype "passive"))
      (node (ref "C4") (pin "2") (pinfunction "2_2") (pintype "passive"))
      (node (ref "IC1") (pin "17") (pinfunction "AVDD_17") (pintype "power_in"))
      (node (ref "IC1") (pin "28") (pinfunction "VDD_28") (pintype "power_in"))
      (node (ref "IC1") (pin "40") (pinfunction "VDD_40") (pintype "power_in"))
      (node (ref "R1") (pin "1") (pinfunction "1_1") (pintype "passive"))
      (node (ref "R38") (pin "3") (pinfunction "E_3") (pintype "passive"))
      (node (ref "R39") (pin "1") (pinfunction "A_1") (pintype "passive"))
      (node (ref "SV1") (pin "2") (pinfunction "2_2") (pintype "passive"))
      (node (ref "X2") (pin "1") (pinfunction "1_1") (pintype "passive"))
    )
    (net (code "68") (name "VSS") (class "Default")
      (node (ref "C1") (pin "1") (pinfunction "1_1") (pintype "passive"))
      (node (ref "C2") (pin "1") (pinfunction "1_1") (pintype "passive"))
      (node (ref "C3") (pin "1") (pinfunction "1_1") (pintype "passive"))
      (node (ref "C4") (pin "1") (pinfunction "1_1") (pintype "passive"))
      (node (ref "IC1") (pin "16") (pinfunction "AVSS_16") (pintype "power_in"))
      (node (ref "IC1") (pin "29") (pinfunction "VSS_29") (pintype "power_in"))
      (node (ref "IC1") (pin "39") (pinfunction "VSS_39") (pintype "power_in"))
      (node (ref "R38") (pin "1") (pinfunction "A_1") (pintype "passive"))
      (node (ref "R39") (pin "3") (pinfunction "E_3") (pintype "passive"))
      (node (ref "SV1") (pin "1") (pinfunction "1_1") (pintype "passive"))
      (node (ref "SV1") (pin "10") (pinfunction "10_10") (pintype "passive"))
      (node (ref "SV1") (pin "16") (pinfunction "16_16") (pintype "passive"))
      (node (ref "SV1") (pin "5") (pinfunction "5_5") (pintype "passive"))
      (node (ref "SV1") (pin "7") (pinfunction "7_7") (pintype "passive"))
      (node (ref "SV1") (pin "8") (pinfunction "8_8") (pintype "passive"))
      (node (ref "SV1") (pin "9") (pinfunction "9_9") (pintype "passive"))
      (node (ref "X2") (pin "2") (pinfunction "1_2") (pintype "passive"))
    )
    (net (code "69") (name "unconnected-(IC1-RA0-Pad19)") (class "Default")
      (node (ref "IC1") (pin "19") (pinfunction "RA0_19") (pintype "bidirectional"))
    )
    (net (code "70") (name "unconnected-(IC1-RA1-Pad20)") (class "Default")
      (node (ref "IC1") (pin "20") (pinfunction "RA1_20") (pintype "bidirectional"))
    )
    (net (code "71") (name "unconnected-(IC1-RA3-Pad31)") (class "Default")
      (node (ref "IC1") (pin "31") (pinfunction "RA3_31") (pintype "bidirectional"))
    )
    (net (code "72") (name "unconnected-(IC1-RA4-Pad34)") (class "Default")
      (node (ref "IC1") (pin "34") (pinfunction "RA4_34") (pintype "bidirectional"))
    )
    (net (code "73") (name "unconnected-(IC1-RB0-Pad21)") (class "Default")
      (node (ref "IC1") (pin "21") (pinfunction "RB0_21") (pintype "bidirectional"))
    )
    (net (code "74") (name "unconnected-(IC1-RB1-Pad22)") (class "Default")
      (node (ref "IC1") (pin "22") (pinfunction "RB1_22") (pintype "bidirectional"))
    )
    (net (code "75") (name "unconnected-(IC1-RB2-Pad23)") (class "Default")
      (node (ref "IC1") (pin "23") (pinfunction "RB2_23") (pintype "bidirectional"))
    )
    (net (code "76") (name "unconnected-(IC1-RB3-Pad24)") (class "Default")
      (node (ref "IC1") (pin "24") (pinfunction "RB3_24") (pintype "bidirectional"))
    )
    (net (code "77") (name "unconnected-(IC1-RB4-Pad33)") (class "Default")
      (node (ref "IC1") (pin "33") (pinfunction "RB4_33") (pintype "bidirectional"))
    )
    (net (code "78") (name "unconnected-(IC1-RB5-Pad41)") (class "Default")
      (node (ref "IC1") (pin "41") (pinfunction "RB5_41") (pintype "bidirectional"))
    )
    (net (code "79") (name "unconnected-(IC1-RB6-Pad42)") (class "Default")
      (node (ref "IC1") (pin "42") (pinfunction "RB6_42") (pintype "bidirectional"))
    )
    (net (code "80") (name "unconnected-(IC1-RB7-Pad43)") (class "Default")
      (node (ref "IC1") (pin "43") (pinfunction "RB7_43") (pintype "bidirectional"))
    )
    (net (code "81") (name "unconnected-(IC1-RB8-Pad44)") (class "Default")
      (node (ref "IC1") (pin "44") (pinfunction "RB8_44") (pintype "bidirectional"))
    )
    (net (code "82") (name "unconnected-(IC1-RB9-Pad1)") (class "Default")
      (node (ref "IC1") (pin "1") (pinfunction "RB9_1") (pintype "bidirectional"))
    )
    (net (code "83") (name "unconnected-(IC1-RB12-Pad10)") (class "Default")
      (node (ref "IC1") (pin "10") (pinfunction "RB12_10") (pintype "bidirectional"))
    )
    (net (code "84") (name "unconnected-(IC1-RB13-Pad11)") (class "Default")
      (node (ref "IC1") (pin "11") (pinfunction "RB13_11") (pintype "bidirectional"))
    )
    (net (code "85") (name "unconnected-(IC1-RB14-Pad14)") (class "Default")
      (node (ref "IC1") (pin "14") (pinfunction "RB14_14") (pintype "bidirectional"))
    )
    (net (code "86") (name "unconnected-(IC1-RB15-Pad15)") (class "Default")
      (node (ref "IC1") (pin "15") (pinfunction "RB15_15") (pintype "bidirectional"))
    )
    (net (code "87") (name "unconnected-(IC1-RC0-Pad25)") (class "Default")
      (node (ref "IC1") (pin "25") (pinfunction "RC0_25") (pintype "bidirectional"))
    )
    (net (code "88") (name "unconnected-(IC1-RC1-Pad26)") (class "Default")
      (node (ref "IC1") (pin "26") (pinfunction "RC1_26") (pintype "bidirectional"))
    )
    (net (code "89") (name "unconnected-(IC1-RC2-Pad27)") (class "Default")
      (node (ref "IC1") (pin "27") (pinfunction "RC2_27") (pintype "bidirectional"))
    )
    (net (code "90") (name "unconnected-(SV1-Pad17)") (class "Default")
      (node (ref "SV1") (pin "17") (pinfunction "17_17") (pintype "passive"))
    )
    (net (code "91") (name "unconnected-(SV1-Pad18)") (class "Default")
      (node (ref "SV1") (pin "18") (pinfunction "18_18") (pintype "passive"))
    )
    (net (code "92") (name "unconnected-(SV1-Pad19)") (class "Default")
      (node (ref "SV1") (pin "19") (pinfunction "19_19") (pintype "passive"))
    )
    (net (code "93") (name "unconnected-(SV1-Pad20)") (class "Default")
      (node (ref "SV1") (pin "20") (pinfunction "20_20") (pintype "passive"))
    )
    (net (code "94") (name "unconnected-(X1-Pad1)") (class "Default")
      (node (ref "X1") (pin "1") (pinfunction "1_1") (pintype "passive"))
    )
    (net (code "95") (name "unconnected-(X1B-1-Pad10)") (class "Default")
      (node (ref "X1") (pin "10") (pinfunction "1_10") (pintype "passive"))
    )
    (net (code "96") (name "unconnected-(X1C-1-Pad2)") (class "Default")
      (node (ref "X1") (pin "2") (pinfunction "1_2") (pintype "passive"))
    )
    (net (code "97") (name "unconnected-(X1D-1-Pad3)") (class "Default")
      (node (ref "X1") (pin "3") (pinfunction "1_3") (pintype "passive"))
    )
    (net (code "98") (name "unconnected-(X1E-1-Pad4)") (class "Default")
      (node (ref "X1") (pin "4") (pinfunction "1_4") (pintype "passive"))
    )
    (net (code "99") (name "unconnected-(X1F-1-Pad5)") (class "Default")
      (node (ref "X1") (pin "5") (pinfunction "1_5") (pintype "passive"))
    )
    (net (code "100") (name "unconnected-(X1G-1-Pad6)") (class "Default")
      (node (ref "X1") (pin "6") (pinfunction "1_6") (pintype "passive"))
    )
    (net (code "101") (name "unconnected-(X1H-1-Pad7)") (class "Default")
      (node (ref "X1") (pin "7") (pinfunction "1_7") (pintype "passive"))
    )
    (net (code "102") (name "unconnected-(X1I-1-Pad8)") (class "Default")
      (node (ref "X1") (pin "8") (pinfunction "1_8") (pintype "passive"))
    )
    (net (code "103") (name "unconnected-(X1J-1-Pad9)") (class "Default")
      (node (ref "X1") (pin "9") (pinfunction "1_9") (pintype "passive"))
    )
    (net (code "104") (name "unconnected-(X4-Pad1)") (class "Default")
      (node (ref "X4") (pin "1") (pinfunction "1_1") (pintype "passive"))
    )
    (net (code "105") (name "unconnected-(X4B-1-Pad10)") (class "Default")
      (node (ref "X4") (pin "10") (pinfunction "1_10") (pintype "passive"))
    )
    (net (code "106") (name "unconnected-(X4C-1-Pad2)") (class "Default")
      (node (ref "X4") (pin "2") (pinfunction "1_2") (pintype "passive"))
    )
    (net (code "107") (name "unconnected-(X4D-1-Pad3)") (class "Default")
      (node (ref "X4") (pin "3") (pinfunction "1_3") (pintype "passive"))
    )
    (net (code "108") (name "unconnected-(X4E-1-Pad4)") (class "Default")
      (node (ref "X4") (pin "4") (pinfunction "1_4") (pintype "passive"))
    )
    (net (code "109") (name "unconnected-(X4F-1-Pad5)") (class "Default")
      (node (ref "X4") (pin "5") (pinfunction "1_5") (pintype "passive"))
    )
    (net (code "110") (name "unconnected-(X4G-1-Pad6)") (class "Default")
      (node (ref "X4") (pin "6") (pinfunction "1_6") (pintype "passive"))
    )
    (net (code "111") (name "unconnected-(X4H-1-Pad7)") (class "Default")
      (node (ref "X4") (pin "7") (pinfunction "1_7") (pintype "passive"))
    )
    (net (code "112") (name "unconnected-(X4I-1-Pad8)") (class "Default")
      (node (ref "X4") (pin "8") (pinfunction "1_8") (pintype "passive"))
    )
    (net (code "113") (name "unconnected-(X4J-1-Pad9)") (class "Default")
      (node (ref "X4") (pin "9") (pinfunction "1_9") (pintype "passive"))
    )
  )
)
